# Accelerometer_3-AXIS_-_BMA180.net
KiCad netlist of a schematic drawn in Altium Designer
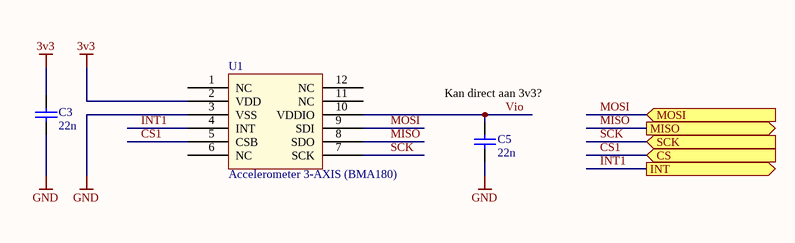
[diagram p0: Accelerometer 3-AXIS - BMA180.SchDoc]

(export (version "E")
  (design (tool "Eeschema 10.0.6"))
  (components
    (comp (ref "C3")
      (value "22n")
      (footprint "C0805")
      (fields (field (name "TOLERANCE") "0.1") (field (name "AUTHOR") "Willy Pietersz"))
      (libsource (lib "OurDb") (part "cap_NonPolar"))
    )
    (comp (ref "C5")
      (value "22n")
      (footprint "C0805")
      (fields (field (name "TOLERANCE") "0.1") (field (name "AUTHOR") "Willy Pietersz"))
      (libsource (lib "OurDb") (part "cap_NonPolar"))
    )
    (comp (ref "U1")
      (value "Accelerometer 3-AXIS (BMA180)")
      (footprint "BMA180")
      (fields (field (name "PART NUMBER") "BMA180"))
      (libsource (lib "OurDb") (part "BMA180"))
    )
  )
  (nets
    (net (code "1") (name "/CS1") (class "Default")
      (node (ref "U1") (pin "5") (pinfunction "CSB_5") (pintype "passive"))
    )
    (net (code "2") (name "/INT1") (class "Default")
      (node (ref "U1") (pin "4") (pinfunction "INT_4") (pintype "passive"))
    )
    (net (code "3") (name "/MISO") (class "Default")
      (node (ref "U1") (pin "8") (pinfunction "SDO_8") (pintype "passive"))
    )
    (net (code "4") (name "/MOSI") (class "Default")
      (node (ref "U1") (pin "9") (pinfunction "SDI_9") (pintype "passive"))
    )
    (net (code "5") (name "/SCK") (class "Default")
      (node (ref "U1") (pin "7") (pinfunction "SCK_7") (pintype "passive"))
    )
    (net (code "6") (name "/Vio") (class "Default")
      (node (ref "C5") (pin "2") (pinfunction "2_2") (pintype "passive"))
      (node (ref "U1") (pin "10") (pinfunction "VDDIO_10") (pintype "passive"))
    )
    (net (code "7") (name "3v3") (class "Default")
      (node (ref "C3") (pin "2") (pinfunction "2_2") (pintype "passive"))
      (node (ref "U1") (pin "2") (pinfunction "VDD_2") (pintype "passive"))
    )
    (net (code "8") (name "GND") (class "Default")
      (node (ref "C3") (pin "1") (pinfunction "1_1") (pintype "passive"))
      (node (ref "C5") (pin "1") (pinfunction "1_1") (pintype "passive"))
      (node (ref "U1") (pin "3") (pinfunction "VSS_3") (pintype "passive"))
    )
    (net (code "9") (name "unconnected-(U1-NC-Pad1)") (class "Default")
      (node (ref "U1") (pin "1") (pinfunction "NC_1") (pintype "passive"))
    )
    (net (code "10") (name "unconnected-(U1-NC-Pad6)") (class "Default")
      (node (ref "U1") (pin "6") (pinfunction "NC_6") (pintype "passive"))
    )
    (net (code "11") (name "unconnected-(U1-NC-Pad11)") (class "Default")
      (node (ref "U1") (pin "11") (pinfunction "NC_11") (pintype "passive"))
    )
    (net (code "12") (name "unconnected-(U1-NC-Pad12)") (class "Default")
      (node (ref "U1") (pin "12") (pinfunction "NC_12") (pintype "passive"))
    )
  )
)
